# Layer.net
KiCad netlist of a schematic drawn in EAGLE
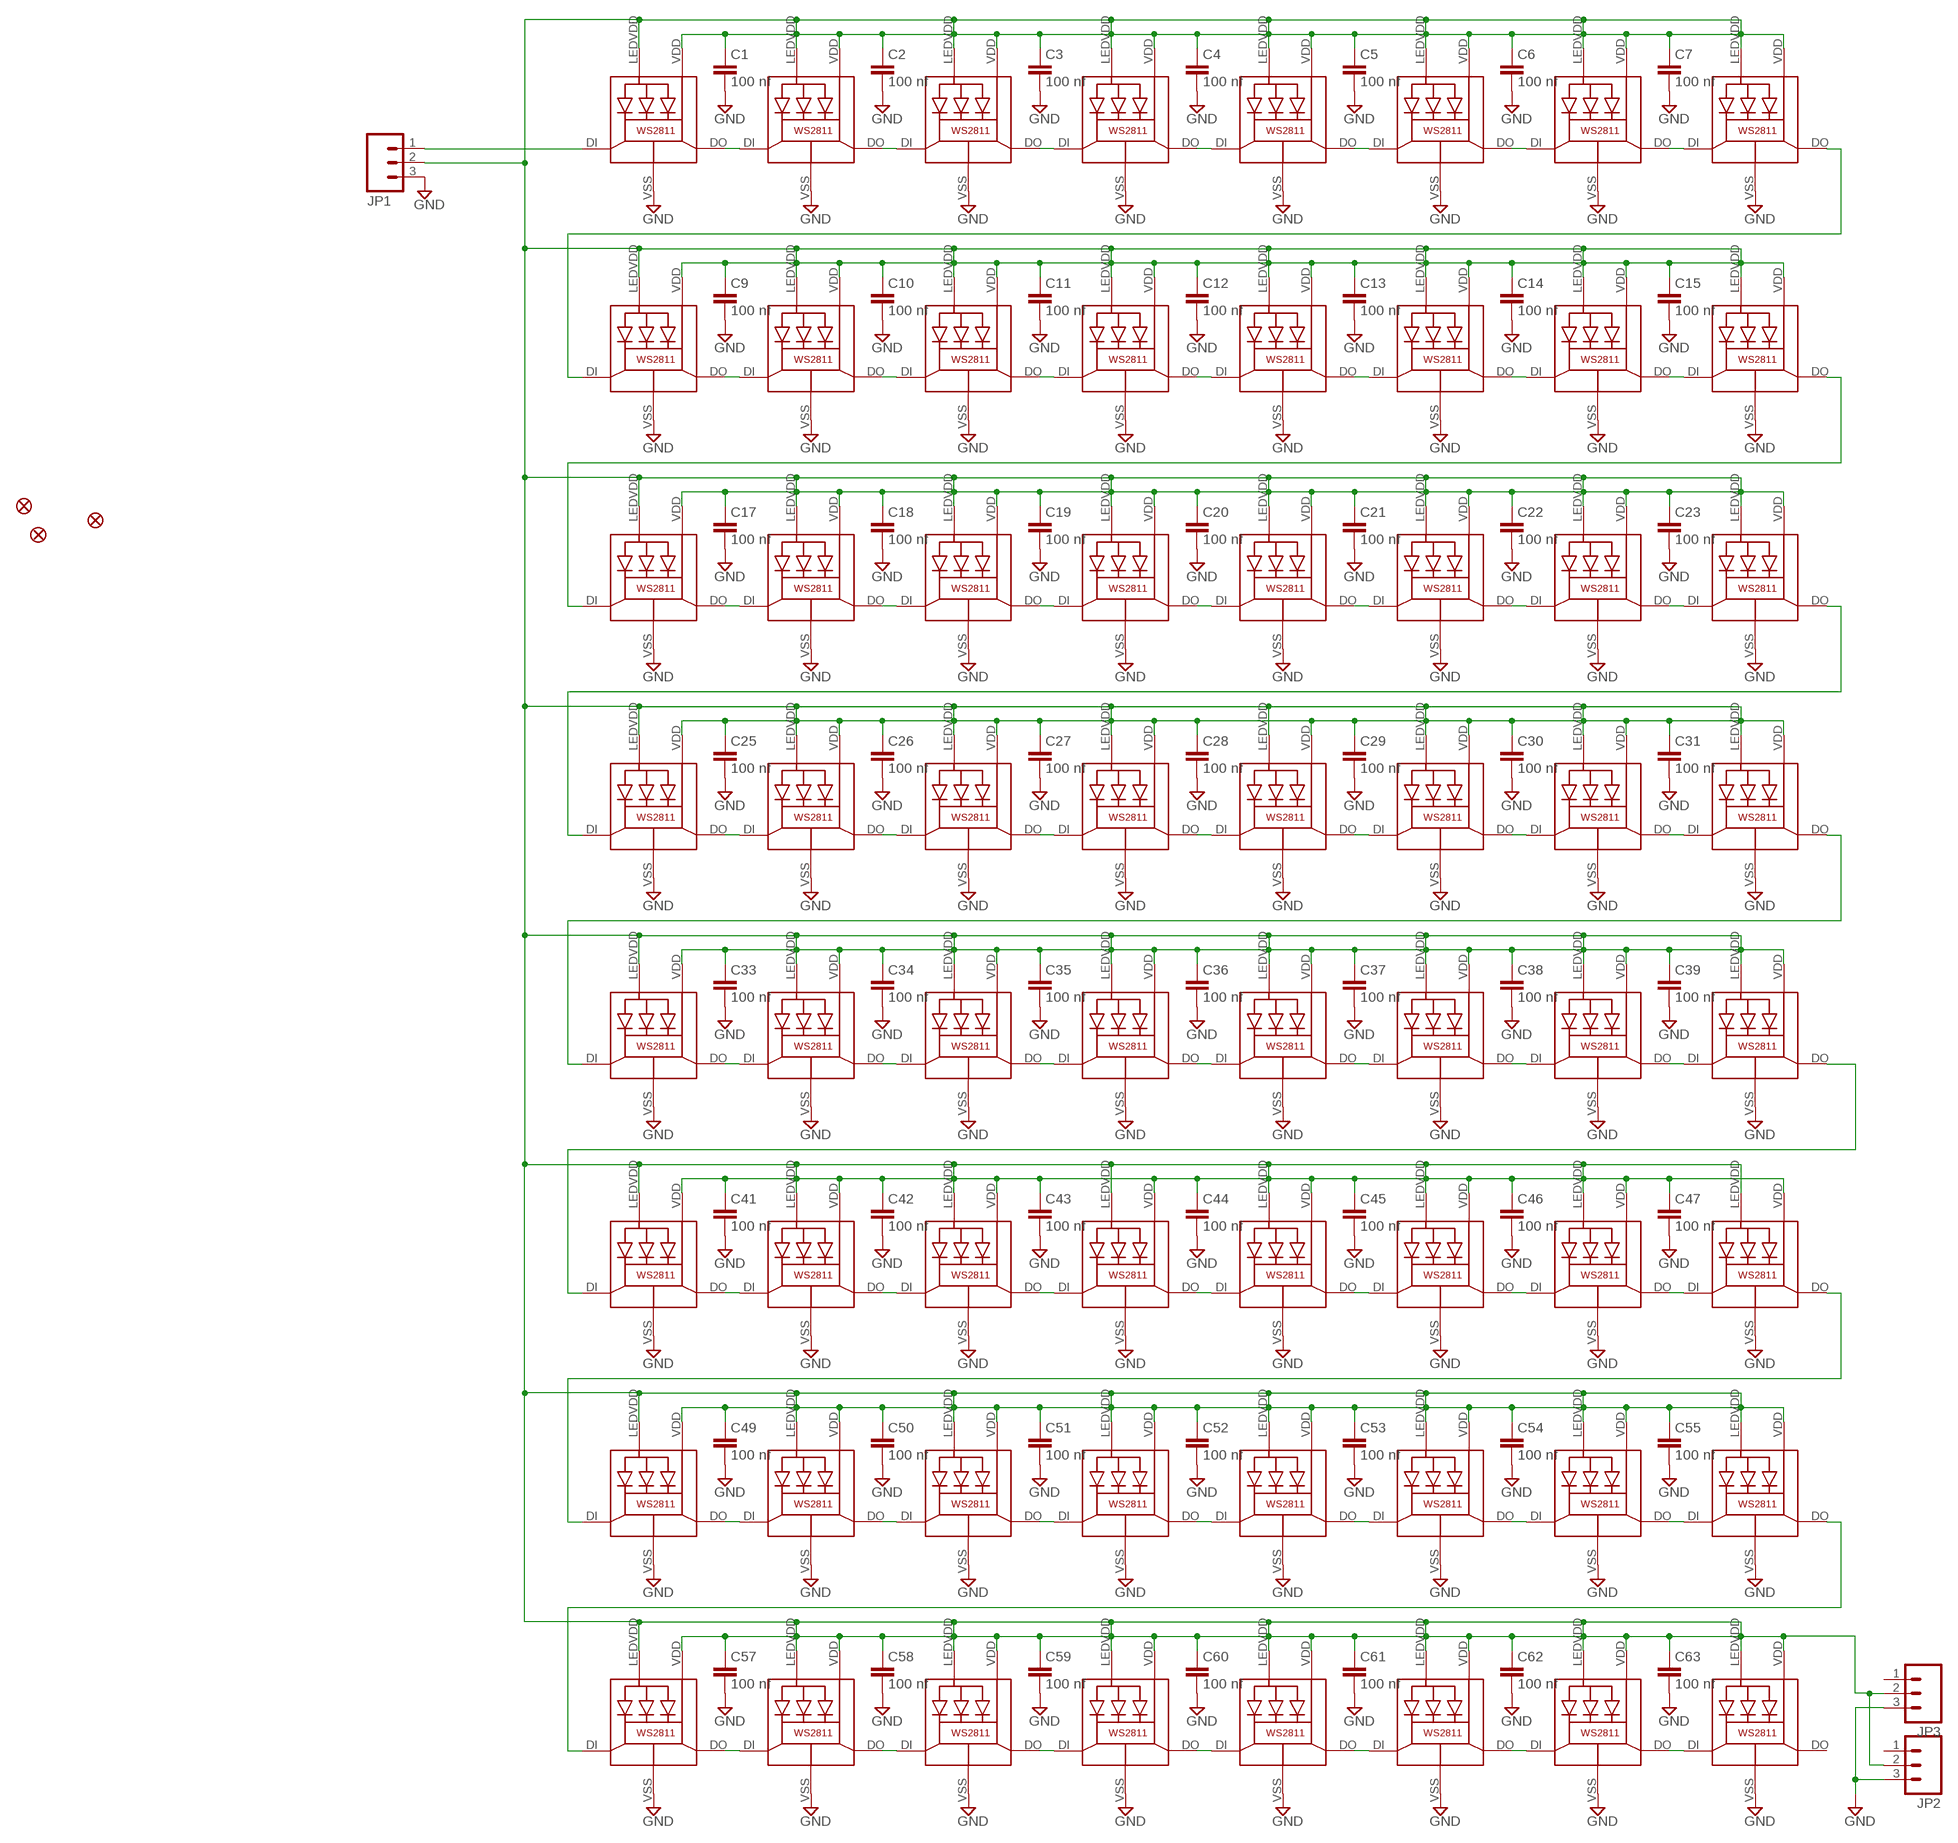
[diagram p0: schematic, sheet 1]

(export (version "E")
  (design (tool "Eeschema 10.0.6"))
  (components
    (comp (ref "C1")
      (value "100 nf")
      (footprint "eagle-import:C0805")
      (libsource (lib "eagle-import") (part "C-EUC0805"))
    )
    (comp (ref "C2")
      (value "100 nf")
      (footprint "eagle-import:C0805")
      (libsource (lib "eagle-import") (part "C-EUC0805"))
    )
    (comp (ref "C3")
      (value "100 nf")
      (footprint "eagle-import:C0805")
      (libsource (lib "eagle-import") (part "C-EUC0805"))
    )
    (comp (ref "C4")
      (value "100 nf")
      (footprint "eagle-import:C0805")
      (libsource (lib "eagle-import") (part "C-EUC0805"))
    )
    (comp (ref "C5")
      (value "100 nf")
      (footprint "eagle-import:C0805")
      (libsource (lib "eagle-import") (part "C-EUC0805"))
    )
    (comp (ref "C6")
      (value "100 nf")
      (footprint "eagle-import:C0805")
      (libsource (lib "eagle-import") (part "C-EUC0805"))
    )
    (comp (ref "C7")
      (value "100 nf")
      (footprint "eagle-import:C0805")
      (libsource (lib "eagle-import") (part "C-EUC0805"))
    )
    (comp (ref "C9")
      (value "100 nf")
      (footprint "eagle-import:C0805")
      (libsource (lib "eagle-import") (part "C-EUC0805"))
    )
    (comp (ref "C10")
      (value "100 nf")
      (footprint "eagle-import:C0805")
      (libsource (lib "eagle-import") (part "C-EUC0805"))
    )
    (comp (ref "C11")
      (value "100 nf")
      (footprint "eagle-import:C0805")
      (libsource (lib "eagle-import") (part "C-EUC0805"))
    )
    (comp (ref "C12")
      (value "100 nf")
      (footprint "eagle-import:C0805")
      (libsource (lib "eagle-import") (part "C-EUC0805"))
    )
    (comp (ref "C13")
      (value "100 nf")
      (footprint "eagle-import:C0805")
      (libsource (lib "eagle-import") (part "C-EUC0805"))
    )
    (comp (ref "C14")
      (value "100 nf")
      (footprint "eagle-import:C0805")
      (libsource (lib "eagle-import") (part "C-EUC0805"))
    )
    (comp (ref "C15")
      (value "100 nf")
      (footprint "eagle-import:C0805")
      (libsource (lib "eagle-import") (part "C-EUC0805"))
    )
    (comp (ref "C17")
      (value "100 nf")
      (footprint "eagle-import:C0805")
      (libsource (lib "eagle-import") (part "C-EUC0805"))
    )
    (comp (ref "C18")
      (value "100 nf")
      (footprint "eagle-import:C0805")
      (libsource (lib "eagle-import") (part "C-EUC0805"))
    )
    (comp (ref "C19")
      (value "100 nf")
      (footprint "eagle-import:C0805")
      (libsource (lib "eagle-import") (part "C-EUC0805"))
    )
    (comp (ref "C20")
      (value "100 nf")
      (footprint "eagle-import:C0805")
      (libsource (lib "eagle-import") (part "C-EUC0805"))
    )
    (comp (ref "C21")
      (value "100 nf")
      (footprint "eagle-import:C0805")
      (libsource (lib "eagle-import") (part "C-EUC0805"))
    )
    (comp (ref "C22")
      (value "100 nf")
      (footprint "eagle-import:C0805")
      (libsource (lib "eagle-import") (part "C-EUC0805"))
    )
    (comp (ref "C23")
      (value "100 nf")
      (footprint "eagle-import:C0805")
      (libsource (lib "eagle-import") (part "C-EUC0805"))
    )
    (comp (ref "C25")
      (value "100 nf")
      (footprint "eagle-import:C0805")
      (libsource (lib "eagle-import") (part "C-EUC0805"))
    )
    (comp (ref "C26")
      (value "100 nf")
      (footprint "eagle-import:C0805")
      (libsource (lib "eagle-import") (part "C-EUC0805"))
    )
    (comp (ref "C27")
      (value "100 nf")
      (footprint "eagle-import:C0805")
      (libsource (lib "eagle-import") (part "C-EUC0805"))
    )
    (comp (ref "C28")
      (value "100 nf")
      (footprint "eagle-import:C0805")
      (libsource (lib "eagle-import") (part "C-EUC0805"))
    )
    (comp (ref "C29")
      (value "100 nf")
      (footprint "eagle-import:C0805")
      (libsource (lib "eagle-import") (part "C-EUC0805"))
    )
    (comp (ref "C30")
      (value "100 nf")
      (footprint "eagle-import:C0805")
      (libsource (lib "eagle-import") (part "C-EUC0805"))
    )
    (comp (ref "C31")
      (value "100 nf")
      (footprint "eagle-import:C0805")
      (libsource (lib "eagle-import") (part "C-EUC0805"))
    )
    (comp (ref "C33")
      (value "100 nf")
      (footprint "eagle-import:C0805")
      (libsource (lib "eagle-import") (part "C-EUC0805"))
    )
    (comp (ref "C34")
      (value "100 nf")
      (footprint "eagle-import:C0805")
      (libsource (lib "eagle-import") (part "C-EUC0805"))
    )
    (comp (ref "C35")
      (value "100 nf")
      (footprint "eagle-import:C0805")
      (libsource (lib "eagle-import") (part "C-EUC0805"))
    )
    (comp (ref "C36")
      (value "100 nf")
      (footprint "eagle-import:C0805")
      (libsource (lib "eagle-import") (part "C-EUC0805"))
    )
    (comp (ref "C37")
      (value "100 nf")
      (footprint "eagle-import:C0805")
      (libsource (lib "eagle-import") (part "C-EUC0805"))
    )
    (comp (ref "C38")
      (value "100 nf")
      (footprint "eagle-import:C0805")
      (libsource (lib "eagle-import") (part "C-EUC0805"))
    )
    (comp (ref "C39")
      (value "100 nf")
      (footprint "eagle-import:C0805")
      (libsource (lib "eagle-import") (part "C-EUC0805"))
    )
    (comp (ref "C41")
      (value "100 nf")
      (footprint "eagle-import:C0805")
      (libsource (lib "eagle-import") (part "C-EUC0805"))
    )
    (comp (ref "C42")
      (value "100 nf")
      (footprint "eagle-import:C0805")
      (libsource (lib "eagle-import") (part "C-EUC0805"))
    )
    (comp (ref "C43")
      (value "100 nf")
      (footprint "eagle-import:C0805")
      (libsource (lib "eagle-import") (part "C-EUC0805"))
    )
    (comp (ref "C44")
      (value "100 nf")
      (footprint "eagle-import:C0805")
      (libsource (lib "eagle-import") (part "C-EUC0805"))
    )
    (comp (ref "C45")
      (value "100 nf")
      (footprint "eagle-import:C0805")
      (libsource (lib "eagle-import") (part "C-EUC0805"))
    )
    (comp (ref "C46")
      (value "100 nf")
      (footprint "eagle-import:C0805")
      (libsource (lib "eagle-import") (part "C-EUC0805"))
    )
    (comp (ref "C47")
      (value "100 nf")
      (footprint "eagle-import:C0805")
      (libsource (lib "eagle-import") (part "C-EUC0805"))
    )
    (comp (ref "C49")
      (value "100 nf")
      (footprint "eagle-import:C0805")
      (libsource (lib "eagle-import") (part "C-EUC0805"))
    )
    (comp (ref "C50")
      (value "100 nf")
      (footprint "eagle-import:C0805")
      (libsource (lib "eagle-import") (part "C-EUC0805"))
    )
    (comp (ref "C51")
      (value "100 nf")
      (footprint "eagle-import:C0805")
      (libsource (lib "eagle-import") (part "C-EUC0805"))
    )
    (comp (ref "C52")
      (value "100 nf")
      (footprint "eagle-import:C0805")
      (libsource (lib "eagle-import") (part "C-EUC0805"))
    )
    (comp (ref "C53")
      (value "100 nf")
      (footprint "eagle-import:C0805")
      (libsource (lib "eagle-import") (part "C-EUC0805"))
    )
    (comp (ref "C54")
      (value "100 nf")
      (footprint "eagle-import:C0805")
      (libsource (lib "eagle-import") (part "C-EUC0805"))
    )
    (comp (ref "C55")
      (value "100 nf")
      (footprint "eagle-import:C0805")
      (libsource (lib "eagle-import") (part "C-EUC0805"))
    )
    (comp (ref "C57")
      (value "100 nf")
      (footprint "eagle-import:C0805")
      (libsource (lib "eagle-import") (part "C-EUC0805"))
    )
    (comp (ref "C58")
      (value "100 nf")
      (footprint "eagle-import:C0805")
      (libsource (lib "eagle-import") (part "C-EUC0805"))
    )
    (comp (ref "C59")
      (value "100 nf")
      (footprint "eagle-import:C0805")
      (libsource (lib "eagle-import") (part "C-EUC0805"))
    )
    (comp (ref "C60")
      (value "100 nf")
      (footprint "eagle-import:C0805")
      (libsource (lib "eagle-import") (part "C-EUC0805"))
    )
    (comp (ref "C61")
      (value "100 nf")
      (footprint "eagle-import:C0805")
      (libsource (lib "eagle-import") (part "C-EUC0805"))
    )
    (comp (ref "C62")
      (value "100 nf")
      (footprint "eagle-import:C0805")
      (libsource (lib "eagle-import") (part "C-EUC0805"))
    )
    (comp (ref "C63")
      (value "100 nf")
      (footprint "eagle-import:C0805")
      (libsource (lib "eagle-import") (part "C-EUC0805"))
    )
    (comp (ref "FID1")
      (value "FIDUCIAL\"\"")
      (footprint "eagle-import:FIDUCIAL_1MM")
      (libsource (lib "eagle-import") (part "FIDUCIAL{dblquote}{dblquote}"))
    )
    (comp (ref "FID2")
      (value "FIDUCIAL\"\"")
      (footprint "eagle-import:FIDUCIAL_1MM")
      (libsource (lib "eagle-import") (part "FIDUCIAL{dblquote}{dblquote}"))
    )
    (comp (ref "FID3")
      (value "FIDUCIAL\"\"")
      (footprint "eagle-import:FIDUCIAL_1MM")
      (libsource (lib "eagle-import") (part "FIDUCIAL{dblquote}{dblquote}"))
    )
    (comp (ref "JP1")
      (value "M03PTH")
      (footprint "eagle-import:1X03")
      (libsource (lib "eagle-import") (part "M03PTH"))
    )
    (comp (ref "JP2")
      (value "M03PTH")
      (footprint "eagle-import:1X03")
      (libsource (lib "eagle-import") (part "M03PTH"))
    )
    (comp (ref "JP3")
      (value "M03PTH")
      (footprint "eagle-import:1X03")
      (libsource (lib "eagle-import") (part "M03PTH"))
    )
    (comp (ref "LED1")
      (value "WS28115050")
      (footprint "eagle-import:WS28115050")
      (fields (field (name "SPICEPREFIX") "X"))
      (libsource (lib "eagle-import") (part "WS28115050"))
    )
    (comp (ref "LED2")
      (value "WS28115050")
      (footprint "eagle-import:WS28115050")
      (libsource (lib "eagle-import") (part "WS28115050"))
    )
    (comp (ref "LED3")
      (value "WS28115050")
      (footprint "eagle-import:WS28115050")
      (libsource (lib "eagle-import") (part "WS28115050"))
    )
    (comp (ref "LED4")
      (value "WS28115050")
      (footprint "eagle-import:WS28115050")
      (libsource (lib "eagle-import") (part "WS28115050"))
    )
    (comp (ref "LED5")
      (value "WS28115050")
      (footprint "eagle-import:WS28115050")
      (libsource (lib "eagle-import") (part "WS28115050"))
    )
    (comp (ref "LED6")
      (value "WS28115050")
      (footprint "eagle-import:WS28115050")
      (libsource (lib "eagle-import") (part "WS28115050"))
    )
    (comp (ref "LED7")
      (value "WS28115050")
      (footprint "eagle-import:WS28115050")
      (libsource (lib "eagle-import") (part "WS28115050"))
    )
    (comp (ref "LED8")
      (value "WS28115050")
      (footprint "eagle-import:WS28115050")
      (libsource (lib "eagle-import") (part "WS28115050"))
    )
    (comp (ref "LED9")
      (value "WS28115050")
      (footprint "eagle-import:WS28115050")
      (libsource (lib "eagle-import") (part "WS28115050"))
    )
    (comp (ref "LED10")
      (value "WS28115050")
      (footprint "eagle-import:WS28115050")
      (libsource (lib "eagle-import") (part "WS28115050"))
    )
    (comp (ref "LED11")
      (value "WS28115050")
      (footprint "eagle-import:WS28115050")
      (libsource (lib "eagle-import") (part "WS28115050"))
    )
    (comp (ref "LED12")
      (value "WS28115050")
      (footprint "eagle-import:WS28115050")
      (libsource (lib "eagle-import") (part "WS28115050"))
    )
    (comp (ref "LED13")
      (value "WS28115050")
      (footprint "eagle-import:WS28115050")
      (libsource (lib "eagle-import") (part "WS28115050"))
    )
    (comp (ref "LED14")
      (value "WS28115050")
      (footprint "eagle-import:WS28115050")
      (libsource (lib "eagle-import") (part "WS28115050"))
    )
    (comp (ref "LED15")
      (value "WS28115050")
      (footprint "eagle-import:WS28115050")
      (libsource (lib "eagle-import") (part "WS28115050"))
    )
    (comp (ref "LED16")
      (value "WS28115050")
      (footprint "eagle-import:WS28115050")
      (libsource (lib "eagle-import") (part "WS28115050"))
    )
    (comp (ref "LED17")
      (value "WS28115050")
      (footprint "eagle-import:WS28115050")
      (libsource (lib "eagle-import") (part "WS28115050"))
    )
    (comp (ref "LED18")
      (value "WS28115050")
      (footprint "eagle-import:WS28115050")
      (libsource (lib "eagle-import") (part "WS28115050"))
    )
    (comp (ref "LED19")
      (value "WS28115050")
      (footprint "eagle-import:WS28115050")
      (libsource (lib "eagle-import") (part "WS28115050"))
    )
    (comp (ref "LED20")
      (value "WS28115050")
      (footprint "eagle-import:WS28115050")
      (libsource (lib "eagle-import") (part "WS28115050"))
    )
    (comp (ref "LED21")
      (value "WS28115050")
      (footprint "eagle-import:WS28115050")
      (libsource (lib "eagle-import") (part "WS28115050"))
    )
    (comp (ref "LED22")
      (value "WS28115050")
      (footprint "eagle-import:WS28115050")
      (libsource (lib "eagle-import") (part "WS28115050"))
    )
    (comp (ref "LED23")
      (value "WS28115050")
      (footprint "eagle-import:WS28115050")
      (libsource (lib "eagle-import") (part "WS28115050"))
    )
    (comp (ref "LED24")
      (value "WS28115050")
      (footprint "eagle-import:WS28115050")
      (libsource (lib "eagle-import") (part "WS28115050"))
    )
    (comp (ref "LED25")
      (value "WS28115050")
      (footprint "eagle-import:WS28115050")
      (libsource (lib "eagle-import") (part "WS28115050"))
    )
    (comp (ref "LED26")
      (value "WS28115050")
      (footprint "eagle-import:WS28115050")
      (libsource (lib "eagle-import") (part "WS28115050"))
    )
    (comp (ref "LED27")
      (value "WS28115050")
      (footprint "eagle-import:WS28115050")
      (libsource (lib "eagle-import") (part "WS28115050"))
    )
    (comp (ref "LED28")
      (value "WS28115050")
      (footprint "eagle-import:WS28115050")
      (libsource (lib "eagle-import") (part "WS28115050"))
    )
    (comp (ref "LED29")
      (value "WS28115050")
      (footprint "eagle-import:WS28115050")
      (libsource (lib "eagle-import") (part "WS28115050"))
    )
    (comp (ref "LED30")
      (value "WS28115050")
      (footprint "eagle-import:WS28115050")
      (libsource (lib "eagle-import") (part "WS28115050"))
    )
    (comp (ref "LED31")
      (value "WS28115050")
      (footprint "eagle-import:WS28115050")
      (libsource (lib "eagle-import") (part "WS28115050"))
    )
    (comp (ref "LED32")
      (value "WS28115050")
      (footprint "eagle-import:WS28115050")
      (libsource (lib "eagle-import") (part "WS28115050"))
    )
    (comp (ref "LED33")
      (value "WS28115050")
      (footprint "eagle-import:WS28115050")
      (libsource (lib "eagle-import") (part "WS28115050"))
    )
    (comp (ref "LED34")
      (value "WS28115050")
      (footprint "eagle-import:WS28115050")
      (libsource (lib "eagle-import") (part "WS28115050"))
    )
    (comp (ref "LED35")
      (value "WS28115050")
      (footprint "eagle-import:WS28115050")
      (libsource (lib "eagle-import") (part "WS28115050"))
    )
    (comp (ref "LED36")
      (value "WS28115050")
      (footprint "eagle-import:WS28115050")
      (libsource (lib "eagle-import") (part "WS28115050"))
    )
    (comp (ref "LED37")
      (value "WS28115050")
      (footprint "eagle-import:WS28115050")
      (libsource (lib "eagle-import") (part "WS28115050"))
    )
    (comp (ref "LED38")
      (value "WS28115050")
      (footprint "eagle-import:WS28115050")
      (libsource (lib "eagle-import") (part "WS28115050"))
    )
    (comp (ref "LED39")
      (value "WS28115050")
      (footprint "eagle-import:WS28115050")
      (libsource (lib "eagle-import") (part "WS28115050"))
    )
    (comp (ref "LED40")
      (value "WS28115050")
      (footprint "eagle-import:WS28115050")
      (libsource (lib "eagle-import") (part "WS28115050"))
    )
    (comp (ref "LED41")
      (value "WS28115050")
      (footprint "eagle-import:WS28115050")
      (libsource (lib "eagle-import") (part "WS28115050"))
    )
    (comp (ref "LED42")
      (value "WS28115050")
      (footprint "eagle-import:WS28115050")
      (libsource (lib "eagle-import") (part "WS28115050"))
    )
    (comp (ref "LED43")
      (value "WS28115050")
      (footprint "eagle-import:WS28115050")
      (libsource (lib "eagle-import") (part "WS28115050"))
    )
    (comp (ref "LED44")
      (value "WS28115050")
      (footprint "eagle-import:WS28115050")
      (libsource (lib "eagle-import") (part "WS28115050"))
    )
    (comp (ref "LED45")
      (value "WS28115050")
      (footprint "eagle-import:WS28115050")
      (libsource (lib "eagle-import") (part "WS28115050"))
    )
    (comp (ref "LED46")
      (value "WS28115050")
      (footprint "eagle-import:WS28115050")
      (libsource (lib "eagle-import") (part "WS28115050"))
    )
    (comp (ref "LED47")
      (value "WS28115050")
      (footprint "eagle-import:WS28115050")
      (libsource (lib "eagle-import") (part "WS28115050"))
    )
    (comp (ref "LED48")
      (value "WS28115050")
      (footprint "eagle-import:WS28115050")
      (libsource (lib "eagle-import") (part "WS28115050"))
    )
    (comp (ref "LED49")
      (value "WS28115050")
      (footprint "eagle-import:WS28115050")
      (libsource (lib "eagle-import") (part "WS28115050"))
    )
    (comp (ref "LED50")
      (value "WS28115050")
      (footprint "eagle-import:WS28115050")
      (libsource (lib "eagle-import") (part "WS28115050"))
    )
    (comp (ref "LED51")
      (value "WS28115050")
      (footprint "eagle-import:WS28115050")
      (libsource (lib "eagle-import") (part "WS28115050"))
    )
    (comp (ref "LED52")
      (value "WS28115050")
      (footprint "eagle-import:WS28115050")
      (libsource (lib "eagle-import") (part "WS28115050"))
    )
    (comp (ref "LED53")
      (value "WS28115050")
      (footprint "eagle-import:WS28115050")
      (libsource (lib "eagle-import") (part "WS28115050"))
    )
    (comp (ref "LED54")
      (value "WS28115050")
      (footprint "eagle-import:WS28115050")
      (libsource (lib "eagle-import") (part "WS28115050"))
    )
    (comp (ref "LED55")
      (value "WS28115050")
      (footprint "eagle-import:WS28115050")
      (libsource (lib "eagle-import") (part "WS28115050"))
    )
    (comp (ref "LED56")
      (value "WS28115050")
      (footprint "eagle-import:WS28115050")
      (libsource (lib "eagle-import") (part "WS28115050"))
    )
    (comp (ref "LED57")
      (value "WS28115050")
      (footprint "eagle-import:WS28115050")
      (libsource (lib "eagle-import") (part "WS28115050"))
    )
    (comp (ref "LED58")
      (value "WS28115050")
      (footprint "eagle-import:WS28115050")
      (libsource (lib "eagle-import") (part "WS28115050"))
    )
    (comp (ref "LED59")
      (value "WS28115050")
      (footprint "eagle-import:WS28115050")
      (libsource (lib "eagle-import") (part "WS28115050"))
    )
    (comp (ref "LED60")
      (value "WS28115050")
      (footprint "eagle-import:WS28115050")
      (libsource (lib "eagle-import") (part "WS28115050"))
    )
    (comp (ref "LED61")
      (value "WS28115050")
      (footprint "eagle-import:WS28115050")
      (libsource (lib "eagle-import") (part "WS28115050"))
    )
    (comp (ref "LED62")
      (value "WS28115050")
      (footprint "eagle-import:WS28115050")
      (libsource (lib "eagle-import") (part "WS28115050"))
    )
    (comp (ref "LED63")
      (value "WS28115050")
      (footprint "eagle-import:WS28115050")
      (libsource (lib "eagle-import") (part "WS28115050"))
    )
    (comp (ref "LED64")
      (value "WS28115050")
      (footprint "eagle-import:WS28115050")
      (libsource (lib "eagle-import") (part "WS28115050"))
    )
  )
  (nets
    (net (code "1") (name "GND") (class "Default")
      (node (ref "C1") (pin "2") (pinfunction "2_2") (pintype "passive"))
      (node (ref "C10") (pin "2") (pinfunction "2_2") (pintype "passive"))
      (node (ref "C11") (pin "2") (pinfunction "2_2") (pintype "passive"))
      (node (ref "C12") (pin "2") (pinfunction "2_2") (pintype "passive"))
      (node (ref "C13") (pin "2") (pinfunction "2_2") (pintype "passive"))
      (node (ref "C14") (pin "2") (pinfunction "2_2") (pintype "passive"))
      (node (ref "C15") (pin "2") (pinfunction "2_2") (pintype "passive"))
      (node (ref "C17") (pin "2") (pinfunction "2_2") (pintype "passive"))
      (node (ref "C18") (pin "2") (pinfunction "2_2") (pintype "passive"))
      (node (ref "C19") (pin "2") (pinfunction "2_2") (pintype "passive"))
      (node (ref "C2") (pin "2") (pinfunction "2_2") (pintype "passive"))
      (node (ref "C20") (pin "2") (pinfunction "2_2") (pintype "passive"))
      (node (ref "C21") (pin "2") (pinfunction "2_2") (pintype "passive"))
      (node (ref "C22") (pin "2") (pinfunction "2_2") (pintype "passive"))
      (node (ref "C23") (pin "2") (pinfunction "2_2") (pintype "passive"))
      (node (ref "C25") (pin "2") (pinfunction "2_2") (pintype "passive"))
      (node (ref "C26") (pin "2") (pinfunction "2_2") (pintype "passive"))
      (node (ref "C27") (pin "2") (pinfunction "2_2") (pintype "passive"))
      (node (ref "C28") (pin "2") (pinfunction "2_2") (pintype "passive"))
      (node (ref "C29") (pin "2") (pinfunction "2_2") (pintype "passive"))
      (node (ref "C3") (pin "2") (pinfunction "2_2") (pintype "passive"))
      (node (ref "C30") (pin "2") (pinfunction "2_2") (pintype "passive"))
      (node (ref "C31") (pin "2") (pinfunction "2_2") (pintype "passive"))
      (node (ref "C33") (pin "2") (pinfunction "2_2") (pintype "passive"))
      (node (ref "C34") (pin "2") (pinfunction "2_2") (pintype "passive"))
      (node (ref "C35") (pin "2") (pinfunction "2_2") (pintype "passive"))
      (node (ref "C36") (pin "2") (pinfunction "2_2") (pintype "passive"))
      (node (ref "C37") (pin "2") (pinfunction "2_2") (pintype "passive"))
      (node (ref "C38") (pin "2") (pinfunction "2_2") (pintype "passive"))
      (node (ref "C39") (pin "2") (pinfunction "2_2") (pintype "passive"))
      (node (ref "C4") (pin "2") (pinfunction "2_2") (pintype "passive"))
      (node (ref "C41") (pin "2") (pinfunction "2_2") (pintype "passive"))
      (node (ref "C42") (pin "2") (pinfunction "2_2") (pintype "passive"))
      (node (ref "C43") (pin "2") (pinfunction "2_2") (pintype "passive"))
      (node (ref "C44") (pin "2") (pinfunction "2_2") (pintype "passive"))
      (node (ref "C45") (pin "2") (pinfunction "2_2") (pintype "passive"))
      (node (ref "C46") (pin "2") (pinfunction "2_2") (pintype "passive"))
      (node (ref "C47") (pin "2") (pinfunction "2_2") (pintype "passive"))
      (node (ref "C49") (pin "2") (pinfunction "2_2") (pintype "passive"))
      (node (ref "C5") (pin "2") (pinfunction "2_2") (pintype "passive"))
      (node (ref "C50") (pin "2") (pinfunction "2_2") (pintype "passive"))
      (node (ref "C51") (pin "2") (pinfunction "2_2") (pintype "passive"))
      (node (ref "C52") (pin "2") (pinfunction "2_2") (pintype "passive"))
      (node (ref "C53") (pin "2") (pinfunction "2_2") (pintype "passive"))
      (node (ref "C54") (pin "2") (pinfunction "2_2") (pintype "passive"))
      (node (ref "C55") (pin "2") (pinfunction "2_2") (pintype "passive"))
      (node (ref "C57") (pin "2") (pinfunction "2_2") (pintype "passive"))
      (node (ref "C58") (pin "2") (pinfunction "2_2") (pintype "passive"))
      (node (ref "C59") (pin "2") (pinfunction "2_2") (pintype "passive"))
      (node (ref "C6") (pin "2") (pinfunction "2_2") (pintype "passive"))
      (node (ref "C60") (pin "2") (pinfunction "2_2") (pintype "passive"))
      (node (ref "C61") (pin "2") (pinfunction "2_2") (pintype "passive"))
      (node (ref "C62") (pin "2") (pinfunction "2_2") (pintype "passive"))
      (node (ref "C63") (pin "2") (pinfunction "2_2") (pintype "passive"))
      (node (ref "C7") (pin "2") (pinfunction "2_2") (pintype "passive"))
      (node (ref "C9") (pin "2") (pinfunction "2_2") (pintype "passive"))
      (node (ref "JP1") (pin "3") (pinfunction "3_3") (pintype "passive"))
      (node (ref "JP2") (pin "3") (pinfunction "3_3") (pintype "passive"))
      (node (ref "JP3") (pin "3") (pinfunction "3_3") (pintype "passive"))
      (node (ref "LED1") (pin "VSS") (pinfunction "GND_VSS") (pintype "power_in"))
      (node (ref "LED10") (pin "VSS") (pinfunction "GND_VSS") (pintype "power_in"))
      (node (ref "LED11") (pin "VSS") (pinfunction "GND_VSS") (pintype "power_in"))
      (node (ref "LED12") (pin "VSS") (pinfunction "GND_VSS") (pintype "power_in"))
      (node (ref "LED13") (pin "VSS") (pinfunction "GND_VSS") (pintype "power_in"))
      (node (ref "LED14") (pin "VSS") (pinfunction "GND_VSS") (pintype "power_in"))
      (node (ref "LED15") (pin "VSS") (pinfunction "GND_VSS") (pintype "power_in"))
      (node (ref "LED16") (pin "VSS") (pinfunction "GND_VSS") (pintype "power_in"))
      (node (ref "LED17") (pin "VSS") (pinfunction "GND_VSS") (pintype "power_in"))
      (node (ref "LED18") (pin "VSS") (pinfunction "GND_VSS") (pintype "power_in"))
      (node (ref "LED19") (pin "VSS") (pinfunction "GND_VSS") (pintype "power_in"))
      (node (ref "LED2") (pin "VSS") (pinfunction "GND_VSS") (pintype "power_in"))
      (node (ref "LED20") (pin "VSS") (pinfunction "GND_VSS") (pintype "power_in"))
      (node (ref "LED21") (pin "VSS") (pinfunction "GND_VSS") (pintype "power_in"))
      (node (ref "LED22") (pin "VSS") (pinfunction "GND_VSS") (pintype "power_in"))
      (node (ref "LED23") (pin "VSS") (pinfunction "GND_VSS") (pintype "power_in"))
      (node (ref "LED24") (pin "VSS") (pinfunction "GND_VSS") (pintype "power_in"))
      (node (ref "LED25") (pin "VSS") (pinfunction "GND_VSS") (pintype "power_in"))
      (node (ref "LED26") (pin "VSS") (pinfunction "GND_VSS") (pintype "power_in"))
      (node (ref "LED27") (pin "VSS") (pinfunction "GND_VSS") (pintype "power_in"))
      (node (ref "LED28") (pin "VSS") (pinfunction "GND_VSS") (pintype "power_in"))
      (node (ref "LED29") (pin "VSS") (pinfunction "GND_VSS") (pintype "power_in"))
      (node (ref "LED3") (pin "VSS") (pinfunction "GND_VSS") (pintype "power_in"))
      (node (ref "LED30") (pin "VSS") (pinfunction "GND_VSS") (pintype "power_in"))
      (node (ref "LED31") (pin "VSS") (pinfunction "GND_VSS") (pintype "power_in"))
      (node (ref "LED32") (pin "VSS") (pinfunction "GND_VSS") (pintype "power_in"))
      (node (ref "LED33") (pin "VSS") (pinfunction "GND_VSS") (pintype "power_in"))
      (node (ref "LED34") (pin "VSS") (pinfunction "GND_VSS") (pintype "power_in"))
      (node (ref "LED35") (pin "VSS") (pinfunction "GND_VSS") (pintype "power_in"))
      (node (ref "LED36") (pin "VSS") (pinfunction "GND_VSS") (pintype "power_in"))
      (node (ref "LED37") (pin "VSS") (pinfunction "GND_VSS") (pintype "power_in"))
      (node (ref "LED38") (pin "VSS") (pinfunction "GND_VSS") (pintype "power_in"))
      (node (ref "LED39") (pin "VSS") (pinfunction "GND_VSS") (pintype "power_in"))
      (node (ref "LED4") (pin "VSS") (pinfunction "GND_VSS") (pintype "power_in"))
      (node (ref "LED40") (pin "VSS") (pinfunction "GND_VSS") (pintype "power_in"))
      (node (ref "LED41") (pin "VSS") (pinfunction "GND_VSS") (pintype "power_in"))
      (node (ref "LED42") (pin "VSS") (pinfunction "GND_VSS") (pintype "power_in"))
      (node (ref "LED43") (pin "VSS") (pinfunction "GND_VSS") (pintype "power_in"))
      (node (ref "LED44") (pin "VSS") (pinfunction "GND_VSS") (pintype "power_in"))
      (node (ref "LED45") (pin "VSS") (pinfunction "GND_VSS") (pintype "power_in"))
      (node (ref "LED46") (pin "VSS") (pinfunction "GND_VSS") (pintype "power_in"))
      (node (ref "LED47") (pin "VSS") (pinfunction "GND_VSS") (pintype "power_in"))
      (node (ref "LED48") (pin "VSS") (pinfunction "GND_VSS") (pintype "power_in"))
      (node (ref "LED49") (pin "VSS") (pinfunction "GND_VSS") (pintype "power_in"))
      (node (ref "LED5") (pin "VSS") (pinfunction "GND_VSS") (pintype "power_in"))
      (node (ref "LED50") (pin "VSS") (pinfunction "GND_VSS") (pintype "power_in"))
      (node (ref "LED51") (pin "VSS") (pinfunction "GND_VSS") (pintype "power_in"))
      (node (ref "LED52") (pin "VSS") (pinfunction "GND_VSS") (pintype "power_in"))
      (node (ref "LED53") (pin "VSS") (pinfunction "GND_VSS") (pintype "power_in"))
      (node (ref "LED54") (pin "VSS") (pinfunction "GND_VSS") (pintype "power_in"))
      (node (ref "LED55") (pin "VSS") (pinfunction "GND_VSS") (pintype "power_in"))
      (node (ref "LED56") (pin "VSS") (pinfunction "GND_VSS") (pintype "power_in"))
      (node (ref "LED57") (pin "VSS") (pinfunction "GND_VSS") (pintype "power_in"))
      (node (ref "LED58") (pin "VSS") (pinfunction "GND_VSS") (pintype "power_in"))
      (node (ref "LED59") (pin "VSS") (pinfunction "GND_VSS") (pintype "power_in"))
      (node (ref "LED6") (pin "VSS") (pinfunction "GND_VSS") (pintype "power_in"))
      (node (ref "LED60") (pin "VSS") (pinfunction "GND_VSS") (pintype "power_in"))
      (node (ref "LED61") (pin "VSS") (pinfunction "GND_VSS") (pintype "power_in"))
      (node (ref "LED62") (pin "VSS") (pinfunction "GND_VSS") (pintype "power_in"))
      (node (ref "LED63") (pin "VSS") (pinfunction "GND_VSS") (pintype "power_in"))
      (node (ref "LED64") (pin "VSS") (pinfunction "GND_VSS") (pintype "power_in"))
      (node (ref "LED7") (pin "VSS") (pinfunction "GND_VSS") (pintype "power_in"))
      (node (ref "LED8") (pin "VSS") (pinfunction "GND_VSS") (pintype "power_in"))
      (node (ref "LED9") (pin "VSS") (pinfunction "GND_VSS") (pintype "power_in"))
    )
    (net (code "2") (name "Net-(C1-Pad1)") (class "Default")
      (node (ref "C1") (pin "1") (pinfunction "1_1") (pintype "passive"))
      (node (ref "C10") (pin "1") (pinfunction "1_1") (pintype "passive"))
      (node (ref "C11") (pin "1") (pinfunction "1_1") (pintype "passive"))
      (node (ref "C12") (pin "1") (pinfunction "1_1") (pintype "passive"))
      (node (ref "C13") (pin "1") (pinfunction "1_1") (pintype "passive"))
      (node (ref "C14") (pin "1") (pinfunction "1_1") (pintype "passive"))
      (node (ref "C15") (pin "1") (pinfunction "1_1") (pintype "passive"))
      (node (ref "C17") (pin "1") (pinfunction "1_1") (pintype "passive"))
      (node (ref "C18") (pin "1") (pinfunction "1_1") (pintype "passive"))
      (node (ref "C19") (pin "1") (pinfunction "1_1") (pintype "passive"))
      (node (ref "C2") (pin "1") (pinfunction "1_1") (pintype "passive"))
      (node (ref "C20") (pin "1") (pinfunction "1_1") (pintype "passive"))
      (node (ref "C21") (pin "1") (pinfunction "1_1") (pintype "passive"))
      (node (ref "C22") (pin "1") (pinfunction "1_1") (pintype "passive"))
      (node (ref "C23") (pin "1") (pinfunction "1_1") (pintype "passive"))
      (node (ref "C25") (pin "1") (pinfunction "1_1") (pintype "passive"))
      (node (ref "C26") (pin "1") (pinfunction "1_1") (pintype "passive"))
      (node (ref "C27") (pin "1") (pinfunction "1_1") (pintype "passive"))
      (node (ref "C28") (pin "1") (pinfunction "1_1") (pintype "passive"))
      (node (ref "C29") (pin "1") (pinfunction "1_1") (pintype "passive"))
      (node (ref "C3") (pin "1") (pinfunction "1_1") (pintype "passive"))
      (node (ref "C30") (pin "1") (pinfunction "1_1") (pintype "passive"))
      (node (ref "C31") (pin "1") (pinfunction "1_1") (pintype "passive"))
      (node (ref "C33") (pin "1") (pinfunction "1_1") (pintype "passive"))
      (node (ref "C34") (pin "1") (pinfunction "1_1") (pintype "passive"))
      (node (ref "C35") (pin "1") (pinfunction "1_1") (pintype "passive"))
      (node (ref "C36") (pin "1") (pinfunction "1_1") (pintype "passive"))
      (node (ref "C37") (pin "1") (pinfunction "1_1") (pintype "passive"))
      (node (ref "C38") (pin "1") (pinfunction "1_1") (pintype "passive"))
      (node (ref "C39") (pin "1") (pinfunction "1_1") (pintype "passive"))
      (node (ref "C4") (pin "1") (pinfunction "1_1") (pintype "passive"))
      (node (ref "C41") (pin "1") (pinfunction "1_1") (pintype "passive"))
      (node (ref "C42") (pin "1") (pinfunction "1_1") (pintype "passive"))
      (node (ref "C43") (pin "1") (pinfunction "1_1") (pintype "passive"))
      (node (ref "C44") (pin "1") (pinfunction "1_1") (pintype "passive"))
      (node (ref "C45") (pin "1") (pinfunction "1_1") (pintype "passive"))
      (node (ref "C46") (pin "1") (pinfunction "1_1") (pintype "passive"))
      (node (ref "C47") (pin "1") (pinfunction "1_1") (pintype "passive"))
      (node (ref "C49") (pin "1") (pinfunction "1_1") (pintype "passive"))
      (node (ref "C5") (pin "1") (pinfunction "1_1") (pintype "passive"))
      (node (ref "C50") (pin "1") (pinfunction "1_1") (pintype "passive"))
      (node (ref "C51") (pin "1") (pinfunction "1_1") (pintype "passive"))
      (node (ref "C52") (pin "1") (pinfunction "1_1") (pintype "passive"))
      (node (ref "C53") (pin "1") (pinfunction "1_1") (pintype "passive"))
      (node (ref "C54") (pin "1") (pinfunction "1_1") (pintype "passive"))
      (node (ref "C55") (pin "1") (pinfunction "1_1") (pintype "passive"))
      (node (ref "C57") (pin "1") (pinfunction "1_1") (pintype "passive"))
      (node (ref "C58") (pin "1") (pinfunction "1_1") (pintype "passive"))
      (node (ref "C59") (pin "1") (pinfunction "1_1") (pintype "passive"))
      (node (ref "C6") (pin "1") (pinfunction "1_1") (pintype "passive"))
      (node (ref "C60") (pin "1") (pinfunction "1_1") (pintype "passive"))
      (node (ref "C61") (pin "1") (pinfunction "1_1") (pintype "passive"))
      (node (ref "C62") (pin "1") (pinfunction "1_1") (pintype "passive"))
      (node (ref "C63") (pin "1") (pinfunction "1_1") (pintype "passive"))
      (node (ref "C7") (pin "1") (pinfunction "1_1") (pintype "passive"))
      (node (ref "C9") (pin "1") (pinfunction "1_1") (pintype "passive"))
      (node (ref "JP1") (pin "2") (pinfunction "2_2") (pintype "passive"))
      (node (ref "JP2") (pin "2") (pinfunction "2_2") (pintype "passive"))
      (node (ref "JP3") (pin "2") (pinfunction "2_2") (pintype "passive"))
      (node (ref "LED1") (pin "LEDVDD") (pinfunction "LEDVDD_LEDVDD") (pintype "power_in"))
      (node (ref "LED1") (pin "VDD") (pinfunction "VDD_VDD") (pintype "power_in"))
      (node (ref "LED10") (pin "LEDVDD") (pinfunction "LEDVDD_LEDVDD") (pintype "power_in"))
      (node (ref "LED10") (pin "VDD") (pinfunction "VDD_VDD") (pintype "power_in"))
      (node (ref "LED11") (pin "LEDVDD") (pinfunction "LEDVDD_LEDVDD") (pintype "power_in"))
      (node (ref "LED11") (pin "VDD") (pinfunction "VDD_VDD") (pintype "power_in"))
      (node (ref "LED12") (pin "LEDVDD") (pinfunction "LEDVDD_LEDVDD") (pintype "power_in"))
      (node (ref "LED12") (pin "VDD") (pinfunction "VDD_VDD") (pintype "power_in"))
      (node (ref "LED13") (pin "LEDVDD") (pinfunction "LEDVDD_LEDVDD") (pintype "power_in"))
      (node (ref "LED13") (pin "VDD") (pinfunction "VDD_VDD") (pintype "power_in"))
      (node (ref "LED14") (pin "LEDVDD") (pinfunction "LEDVDD_LEDVDD") (pintype "power_in"))
      (node (ref "LED14") (pin "VDD") (pinfunction "VDD_VDD") (pintype "power_in"))
      (node (ref "LED15") (pin "LEDVDD") (pinfunction "LEDVDD_LEDVDD") (pintype "power_in"))
      (node (ref "LED15") (pin "VDD") (pinfunction "VDD_VDD") (pintype "power_in"))
      (node (ref "LED16") (pin "LEDVDD") (pinfunction "LEDVDD_LEDVDD") (pintype "power_in"))
      (node (ref "LED16") (pin "VDD") (pinfunction "VDD_VDD") (pintype "power_in"))
      (node (ref "LED17") (pin "LEDVDD") (pinfunction "LEDVDD_LEDVDD") (pintype "power_in"))
      (node (ref "LED17") (pin "VDD") (pinfunction "VDD_VDD") (pintype "power_in"))
      (node (ref "LED18") (pin "LEDVDD") (pinfunction "LEDVDD_LEDVDD") (pintype "power_in"))
      (node (ref "LED18") (pin "VDD") (pinfunction "VDD_VDD") (pintype "power_in"))
      (node (ref "LED19") (pin "LEDVDD") (pinfunction "LEDVDD_LEDVDD") (pintype "power_in"))
      (node (ref "LED19") (pin "VDD") (pinfunction "VDD_VDD") (pintype "power_in"))
      (node (ref "LED2") (pin "LEDVDD") (pinfunction "LEDVDD_LEDVDD") (pintype "power_in"))
      (node (ref "LED2") (pin "VDD") (pinfunction "VDD_VDD") (pintype "power_in"))
      (node (ref "LED20") (pin "LEDVDD") (pinfunction "LEDVDD_LEDVDD") (pintype "power_in"))
      (node (ref "LED20") (pin "VDD") (pinfunction "VDD_VDD") (pintype "power_in"))
      (node (ref "LED21") (pin "LEDVDD") (pinfunction "LEDVDD_LEDVDD") (pintype "power_in"))
      (node (ref "LED21") (pin "VDD") (pinfunction "VDD_VDD") (pintype "power_in"))
      (node (ref "LED22") (pin "LEDVDD") (pinfunction "LEDVDD_LEDVDD") (pintype "power_in"))
      (node (ref "LED22") (pin "VDD") (pinfunction "VDD_VDD") (pintype "power_in"))
      (node (ref "LED23") (pin "LEDVDD") (pinfunction "LEDVDD_LEDVDD") (pintype "power_in"))
      (node (ref "LED23") (pin "VDD") (pinfunction "VDD_VDD") (pintype "power_in"))
      (node (ref "LED24") (pin "LEDVDD") (pinfunction "LEDVDD_LEDVDD") (pintype "power_in"))
      (node (ref "LED24") (pin "VDD") (pinfunction "VDD_VDD") (pintype "power_in"))
      (node (ref "LED25") (pin "LEDVDD") (pinfunction "LEDVDD_LEDVDD") (pintype "power_in"))
      (node (ref "LED25") (pin "VDD") (pinfunction "VDD_VDD") (pintype "power_in"))
      (node (ref "LED26") (pin "LEDVDD") (pinfunction "LEDVDD_LEDVDD") (pintype "power_in"))
      (node (ref "LED26") (pin "VDD") (pinfunction "VDD_VDD") (pintype "power_in"))
      (node (ref "LED27") (pin "LEDVDD") (pinfunction "LEDVDD_LEDVDD") (pintype "power_in"))
      (node (ref "LED27") (pin "VDD") (pinfunction "VDD_VDD") (pintype "power_in"))
      (node (ref "LED28") (pin "LEDVDD") (pinfunction "LEDVDD_LEDVDD") (pintype "power_in"))
      (node (ref "LED28") (pin "VDD") (pinfunction "VDD_VDD") (pintype "power_in"))
      (node (ref "LED29") (pin "LEDVDD") (pinfunction "LEDVDD_LEDVDD") (pintype "power_in"))
      (node (ref "LED29") (pin "VDD") (pinfunction "VDD_VDD") (pintype "power_in"))
      (node (ref "LED3") (pin "LEDVDD") (pinfunction "LEDVDD_LEDVDD") (pintype "power_in"))
      (node (ref "LED3") (pin "VDD") (pinfunction "VDD_VDD") (pintype "power_in"))
      (node (ref "LED30") (pin "LEDVDD") (pinfunction "LEDVDD_LEDVDD") (pintype "power_in"))
      (node (ref "LED30") (pin "VDD") (pinfunction "VDD_VDD") (pintype "power_in"))
      (node (ref "LED31") (pin "LEDVDD") (pinfunction "LEDVDD_LEDVDD") (pintype "power_in"))
      (node (ref "LED31") (pin "VDD") (pinfunction "VDD_VDD") (pintype "power_in"))
      (node (ref "LED32") (pin "LEDVDD") (pinfunction "LEDVDD_LEDVDD") (pintype "power_in"))
      (node (ref "LED32") (pin "VDD") (pinfunction "VDD_VDD") (pintype "power_in"))
      (node (ref "LED33") (pin "LEDVDD") (pinfunction "LEDVDD_LEDVDD") (pintype "power_in"))
      (node (ref "LED33") (pin "VDD") (pinfunction "VDD_VDD") (pintype "power_in"))
      (node (ref "LED34") (pin "LEDVDD") (pinfunction "LEDVDD_LEDVDD") (pintype "power_in"))
      (node (ref "LED34") (pin "VDD") (pinfunction "VDD_VDD") (pintype "power_in"))
      (node (ref "LED35") (pin "LEDVDD") (pinfunction "LEDVDD_LEDVDD") (pintype "power_in"))
      (node (ref "LED35") (pin "VDD") (pinfunction "VDD_VDD") (pintype "power_in"))
      (node (ref "LED36") (pin "LEDVDD") (pinfunction "LEDVDD_LEDVDD") (pintype "power_in"))
      (node (ref "LED36") (pin "VDD") (pinfunction "VDD_VDD") (pintype "power_in"))
      (node (ref "LED37") (pin "LEDVDD") (pinfunction "LEDVDD_LEDVDD") (pintype "power_in"))
      (node (ref "LED37") (pin "VDD") (pinfunction "VDD_VDD") (pintype "power_in"))
      (node (ref "LED38") (pin "LEDVDD") (pinfunction "LEDVDD_LEDVDD") (pintype "power_in"))
      (node (ref "LED38") (pin "VDD") (pinfunction "VDD_VDD") (pintype "power_in"))
      (node (ref "LED39") (pin "LEDVDD") (pinfunction "LEDVDD_LEDVDD") (pintype "power_in"))
      (node (ref "LED39") (pin "VDD") (pinfunction "VDD_VDD") (pintype "power_in"))
      (node (ref "LED4") (pin "LEDVDD") (pinfunction "LEDVDD_LEDVDD") (pintype "power_in"))
      (node (ref "LED4") (pin "VDD") (pinfunction "VDD_VDD") (pintype "power_in"))
      (node (ref "LED40") (pin "LEDVDD") (pinfunction "LEDVDD_LEDVDD") (pintype "power_in"))
      (node (ref "LED40") (pin "VDD") (pinfunction "VDD_VDD") (pintype "power_in"))
      (node (ref "LED41") (pin "LEDVDD") (pinfunction "LEDVDD_LEDVDD") (pintype "power_in"))
      (node (ref "LED41") (pin "VDD") (pinfunction "VDD_VDD") (pintype "power_in"))
      (node (ref "LED42") (pin "LEDVDD") (pinfunction "LEDVDD_LEDVDD") (pintype "power_in"))
      (node (ref "LED42") (pin "VDD") (pinfunction "VDD_VDD") (pintype "power_in"))
      (node (ref "LED43") (pin "LEDVDD") (pinfunction "LEDVDD_LEDVDD") (pintype "power_in"))
      (node (ref "LED43") (pin "VDD") (pinfunction "VDD_VDD") (pintype "power_in"))
      (node (ref "LED44") (pin "LEDVDD") (pinfunction "LEDVDD_LEDVDD") (pintype "power_in"))
      (node (ref "LED44") (pin "VDD") (pinfunction "VDD_VDD") (pintype "power_in"))
      (node (ref "LED45") (pin "LEDVDD") (pinfunction "LEDVDD_LEDVDD") (pintype "power_in"))
      (node (ref "LED45") (pin "VDD") (pinfunction "VDD_VDD") (pintype "power_in"))
      (node (ref "LED46") (pin "LEDVDD") (pinfunction "LEDVDD_LEDVDD") (pintype "power_in"))
      (node (ref "LED46") (pin "VDD") (pinfunction "VDD_VDD") (pintype "power_in"))
      (node (ref "LED47") (pin "LEDVDD") (pinfunction "LEDVDD_LEDVDD") (pintype "power_in"))
      (node (ref "LED47") (pin "VDD") (pinfunction "VDD_VDD") (pintype "power_in"))
      (node (ref "LED48") (pin "LEDVDD") (pinfunction "LEDVDD_LEDVDD") (pintype "power_in"))
      (node (ref "LED48") (pin "VDD") (pinfunction "VDD_VDD") (pintype "power_in"))
      (node (ref "LED49") (pin "LEDVDD") (pinfunction "LEDVDD_LEDVDD") (pintype "power_in"))
      (node (ref "LED49") (pin "VDD") (pinfunction "VDD_VDD") (pintype "power_in"))
      (node (ref "LED5") (pin "LEDVDD") (pinfunction "LEDVDD_LEDVDD") (pintype "power_in"))
      (node (ref "LED5") (pin "VDD") (pinfunction "VDD_VDD") (pintype "power_in"))
      (node (ref "LED50") (pin "LEDVDD") (pinfunction "LEDVDD_LEDVDD") (pintype "power_in"))
      (node (ref "LED50") (pin "VDD") (pinfunction "VDD_VDD") (pintype "power_in"))
      (node (ref "LED51") (pin "LEDVDD") (pinfunction "LEDVDD_LEDVDD") (pintype "power_in"))
      (node (ref "LED51") (pin "VDD") (pinfunction "VDD_VDD") (pintype "power_in"))
      (node (ref "LED52") (pin "LEDVDD") (pinfunction "LEDVDD_LEDVDD") (pintype "power_in"))
      (node (ref "LED52") (pin "VDD") (pinfunction "VDD_VDD") (pintype "power_in"))
      (node (ref "LED53") (pin "LEDVDD") (pinfunction "LEDVDD_LEDVDD") (pintype "power_in"))
      (node (ref "LED53") (pin "VDD") (pinfunction "VDD_VDD") (pintype "power_in"))
      (node (ref "LED54") (pin "LEDVDD") (pinfunction "LEDVDD_LEDVDD") (pintype "power_in"))
      (node (ref "LED54") (pin "VDD") (pinfunction "VDD_VDD") (pintype "power_in"))
      (node (ref "LED55") (pin "LEDVDD") (pinfunction "LEDVDD_LEDVDD") (pintype "power_in"))
      (node (ref "LED55") (pin "VDD") (pinfunction "VDD_VDD") (pintype "power_in"))
      (node (ref "LED56") (pin "LEDVDD") (pinfunction "LEDVDD_LEDVDD") (pintype "power_in"))
      (node (ref "LED56") (pin "VDD") (pinfunction "VDD_VDD") (pintype "power_in"))
      (node (ref "LED57") (pin "LEDVDD") (pinfunction "LEDVDD_LEDVDD") (pintype "power_in"))
      (node (ref "LED57") (pin "VDD") (pinfunction "VDD_VDD") (pintype "power_in"))
      (node (ref "LED58") (pin "LEDVDD") (pinfunction "LEDVDD_LEDVDD") (pintype "power_in"))
      (node (ref "LED58") (pin "VDD") (pinfunction "VDD_VDD") (pintype "power_in"))
      (node (ref "LED59") (pin "LEDVDD") (pinfunction "LEDVDD_LEDVDD") (pintype "power_in"))
      (node (ref "LED59") (pin "VDD") (pinfunction "VDD_VDD") (pintype "power_in"))
      (node (ref "LED6") (pin "LEDVDD") (pinfunction "LEDVDD_LEDVDD") (pintype "power_in"))
      (node (ref "LED6") (pin "VDD") (pinfunction "VDD_VDD") (pintype "power_in"))
      (node (ref "LED60") (pin "LEDVDD") (pinfunction "LEDVDD_LEDVDD") (pintype "power_in"))
      (node (ref "LED60") (pin "VDD") (pinfunction "VDD_VDD") (pintype "power_in"))
      (node (ref "LED61") (pin "LEDVDD") (pinfunction "LEDVDD_LEDVDD") (pintype "power_in"))
      (node (ref "LED61") (pin "VDD") (pinfunction "VDD_VDD") (pintype "power_in"))
      (node (ref "LED62") (pin "LEDVDD") (pinfunction "LEDVDD_LEDVDD") (pintype "power_in"))
      (node (ref "LED62") (pin "VDD") (pinfunction "VDD_VDD") (pintype "power_in"))
      (node (ref "LED63") (pin "LEDVDD") (pinfunction "LEDVDD_LEDVDD") (pintype "power_in"))
      (node (ref "LED63") (pin "VDD") (pinfunction "VDD_VDD") (pintype "power_in"))
      (node (ref "LED64") (pin "LEDVDD") (pinfunction "LEDVDD_LEDVDD") (pintype "power_in"))
      (node (ref "LED64") (pin "VDD") (pinfunction "VDD_VDD") (pintype "power_in"))
      (node (ref "LED7") (pin "LEDVDD") (pinfunction "LEDVDD_LEDVDD") (pintype "power_in"))
      (node (ref "LED7") (pin "VDD") (pinfunction "VDD_VDD") (pintype "power_in"))
      (node (ref "LED8") (pin "LEDVDD") (pinfunction "LEDVDD_LEDVDD") (pintype "power_in"))
      (node (ref "LED8") (pin "VDD") (pinfunction "VDD_VDD") (pintype "power_in"))
      (node (ref "LED9") (pin "LEDVDD") (pinfunction "LEDVDD_LEDVDD") (pintype "power_in"))
      (node (ref "LED9") (pin "VDD") (pinfunction "VDD_VDD") (pintype "power_in"))
    )
    (net (code "3") (name "Net-(JP1-Pad1)") (class "Default")
      (node (ref "JP1") (pin "1") (pinfunction "1_1") (pintype "passive"))
      (node (ref "LED1") (pin "DI") (pinfunction "DI_DI") (pintype "input"))
    )
    (net (code "4") (name "Net-(LED1-PadDO)") (class "Default")
      (node (ref "LED1") (pin "DO") (pinfunction "DO_DO") (pintype "output"))
      (node (ref "LED2") (pin "DI") (pinfunction "DI_DI") (pintype "input"))
    )
    (net (code "5") (name "Net-(LED2-PadDO)") (class "Default")
      (node (ref "LED2") (pin "DO") (pinfunction "DO_DO") (pintype "output"))
      (node (ref "LED3") (pin "DI") (pinfunction "DI_DI") (pintype "input"))
    )
    (net (code "6") (name "Net-(LED3-PadDO)") (class "Default")
      (node (ref "LED3") (pin "DO") (pinfunction "DO_DO") (pintype "output"))
      (node (ref "LED4") (pin "DI") (pinfunction "DI_DI") (pintype "input"))
    )
    (net (code "7") (name "Net-(LED4-PadDO)") (class "Default")
      (node (ref "LED4") (pin "DO") (pinfunction "DO_DO") (pintype "output"))
      (node (ref "LED5") (pin "DI") (pinfunction "DI_DI") (pintype "input"))
    )
    (net (code "8") (name "Net-(LED5-PadDO)") (class "Default")
      (node (ref "LED5") (pin "DO") (pinfunction "DO_DO") (pintype "output"))
      (node (ref "LED6") (pin "DI") (pinfunction "DI_DI") (pintype "input"))
    )
    (net (code "9") (name "Net-(LED6-PadDO)") (class "Default")
      (node (ref "LED6") (pin "DO") (pinfunction "DO_DO") (pintype "output"))
      (node (ref "LED7") (pin "DI") (pinfunction "DI_DI") (pintype "input"))
    )
    (net (code "10") (name "Net-(LED7-PadDO)") (class "Default")
      (node (ref "LED7") (pin "DO") (pinfunction "DO_DO") (pintype "output"))
      (node (ref "LED8") (pin "DI") (pinfunction "DI_DI") (pintype "input"))
    )
    (net (code "11") (name "Net-(LED8-PadDO)") (class "Default")
      (node (ref "LED8") (pin "DO") (pinfunction "DO_DO") (pintype "output"))
      (node (ref "LED9") (pin "DI") (pinfunction "DI_DI") (pintype "input"))
    )
    (net (code "12") (name "Net-(LED10-PadDI)") (class "Default")
      (node (ref "LED10") (pin "DI") (pinfunction "DI_DI") (pintype "input"))
      (node (ref "LED9") (pin "DO") (pinfunction "DO_DO") (pintype "output"))
    )
    (net (code "13") (name "Net-(LED10-PadDO)") (class "Default")
      (node (ref "LED10") (pin "DO") (pinfunction "DO_DO") (pintype "output"))
      (node (ref "LED11") (pin "DI") (pinfunction "DI_DI") (pintype "input"))
    )
    (net (code "14") (name "Net-(LED11-PadDO)") (class "Default")
      (node (ref "LED11") (pin "DO") (pinfunction "DO_DO") (pintype "output"))
      (node (ref "LED12") (pin "DI") (pinfunction "DI_DI") (pintype "input"))
    )
    (net (code "15") (name "Net-(LED12-PadDO)") (class "Default")
      (node (ref "LED12") (pin "DO") (pinfunction "DO_DO") (pintype "output"))
      (node (ref "LED13") (pin "DI") (pinfunction "DI_DI") (pintype "input"))
    )
    (net (code "16") (name "Net-(LED13-PadDO)") (class "Default")
      (node (ref "LED13") (pin "DO") (pinfunction "DO_DO") (pintype "output"))
      (node (ref "LED14") (pin "DI") (pinfunction "DI_DI") (pintype "input"))
    )
    (net (code "17") (name "Net-(LED14-PadDO)") (class "Default")
      (node (ref "LED14") (pin "DO") (pinfunction "DO_DO") (pintype "output"))
      (node (ref "LED15") (pin "DI") (pinfunction "DI_DI") (pintype "input"))
    )
    (net (code "18") (name "Net-(LED15-PadDO)") (class "Default")
      (node (ref "LED15") (pin "DO") (pinfunction "DO_DO") (pintype "output"))
      (node (ref "LED16") (pin "DI") (pinfunction "DI_DI") (pintype "input"))
    )
    (net (code "19") (name "Net-(LED16-PadDO)") (class "Default")
      (node (ref "LED16") (pin "DO") (pinfunction "DO_DO") (pintype "output"))
      (node (ref "LED17") (pin "DI") (pinfunction "DI_DI") (pintype "input"))
    )
    (net (code "20") (name "Net-(LED17-PadDO)") (class "Default")
      (node (ref "LED17") (pin "DO") (pinfunction "DO_DO") (pintype "output"))
      (node (ref "LED18") (pin "DI") (pinfunction "DI_DI") (pintype "input"))
    )
    (net (code "21") (name "Net-(LED18-PadDO)") (class "Default")
      (node (ref "LED18") (pin "DO") (pinfunction "DO_DO") (pintype "output"))
      (node (ref "LED19") (pin "DI") (pinfunction "DI_DI") (pintype "input"))
    )
    (net (code "22") (name "Net-(LED19-PadDO)") (class "Default")
      (node (ref "LED19") (pin "DO") (pinfunction "DO_DO") (pintype "output"))
      (node (ref "LED20") (pin "DI") (pinfunction "DI_DI") (pintype "input"))
    )
    (net (code "23") (name "Net-(LED20-PadDO)") (class "Default")
      (node (ref "LED20") (pin "DO") (pinfunction "DO_DO") (pintype "output"))
      (node (ref "LED21") (pin "DI") (pinfunction "DI_DI") (pintype "input"))
    )
    (net (code "24") (name "Net-(LED21-PadDO)") (class "Default")
      (node (ref "LED21") (pin "DO") (pinfunction "DO_DO") (pintype "output"))
      (node (ref "LED22") (pin "DI") (pinfunction "DI_DI") (pintype "input"))
    )
    (net (code "25") (name "Net-(LED22-PadDO)") (class "Default")
      (node (ref "LED22") (pin "DO") (pinfunction "DO_DO") (pintype "output"))
      (node (ref "LED23") (pin "DI") (pinfunction "DI_DI") (pintype "input"))
    )
    (net (code "26") (name "Net-(LED23-PadDO)") (class "Default")
      (node (ref "LED23") (pin "DO") (pinfunction "DO_DO") (pintype "output"))
      (node (ref "LED24") (pin "DI") (pinfunction "DI_DI") (pintype "input"))
    )
    (net (code "27") (name "Net-(LED24-PadDO)") (class "Default")
      (node (ref "LED24") (pin "DO") (pinfunction "DO_DO") (pintype "output"))
      (node (ref "LED25") (pin "DI") (pinfunction "DI_DI") (pintype "input"))
    )
    (net (code "28") (name "Net-(LED25-PadDO)") (class "Default")
      (node (ref "LED25") (pin "DO") (pinfunction "DO_DO") (pintype "output"))
      (node (ref "LED26") (pin "DI") (pinfunction "DI_DI") (pintype "input"))
    )
    (net (code "29") (name "Net-(LED26-PadDO)") (class "Default")
      (node (ref "LED26") (pin "DO") (pinfunction "DO_DO") (pintype "output"))
      (node (ref "LED27") (pin "DI") (pinfunction "DI_DI") (pintype "input"))
    )
    (net (code "30") (name "Net-(LED27-PadDO)") (class "Default")
      (node (ref "LED27") (pin "DO") (pinfunction "DO_DO") (pintype "output"))
      (node (ref "LED28") (pin "DI") (pinfunction "DI_DI") (pintype "input"))
    )
    (net (code "31") (name "Net-(LED28-PadDO)") (class "Default")
      (node (ref "LED28") (pin "DO") (pinfunction "DO_DO") (pintype "output"))
      (node (ref "LED29") (pin "DI") (pinfunction "DI_DI") (pintype "input"))
    )
    (net (code "32") (name "Net-(LED29-PadDO)") (class "Default")
      (node (ref "LED29") (pin "DO") (pinfunction "DO_DO") (pintype "output"))
      (node (ref "LED30") (pin "DI") (pinfunction "DI_DI") (pintype "input"))
    )
    (net (code "33") (name "Net-(LED30-PadDO)") (class "Default")
      (node (ref "LED30") (pin "DO") (pinfunction "DO_DO") (pintype "output"))
      (node (ref "LED31") (pin "DI") (pinfunction "DI_DI") (pintype "input"))
    )
    (net (code "34") (name "Net-(LED31-PadDO)") (class "Default")
      (node (ref "LED31") (pin "DO") (pinfunction "DO_DO") (pintype "output"))
      (node (ref "LED32") (pin "DI") (pinfunction "DI_DI") (pintype "input"))
    )
    (net (code "35") (name "Net-(LED32-PadDO)") (class "Default")
      (node (ref "LED32") (pin "DO") (pinfunction "DO_DO") (pintype "output"))
      (node (ref "LED33") (pin "DI") (pinfunction "DI_DI") (pintype "input"))
    )
    (net (code "36") (name "Net-(LED33-PadDO)") (class "Default")
      (node (ref "LED33") (pin "DO") (pinfunction "DO_DO") (pintype "output"))
      (node (ref "LED34") (pin "DI") (pinfunction "DI_DI") (pintype "input"))
    )
    (net (code "37") (name "Net-(LED34-PadDO)") (class "Default")
      (node (ref "LED34") (pin "DO") (pinfunction "DO_DO") (pintype "output"))
      (node (ref "LED35") (pin "DI") (pinfunction "DI_DI") (pintype "input"))
    )
    (net (code "38") (name "Net-(LED35-PadDO)") (class "Default")
      (node (ref "LED35") (pin "DO") (pinfunction "DO_DO") (pintype "output"))
      (node (ref "LED36") (pin "DI") (pinfunction "DI_DI") (pintype "input"))
    )
    (net (code "39") (name "Net-(LED36-PadDO)") (class "Default")
      (node (ref "LED36") (pin "DO") (pinfunction "DO_DO") (pintype "output"))
      (node (ref "LED37") (pin "DI") (pinfunction "DI_DI") (pintype "input"))
    )
    (net (code "40") (name "Net-(LED37-PadDO)") (class "Default")
      (node (ref "LED37") (pin "DO") (pinfunction "DO_DO") (pintype "output"))
      (node (ref "LED38") (pin "DI") (pinfunction "DI_DI") (pintype "input"))
    )
    (net (code "41") (name "Net-(LED38-PadDO)") (class "Default")
      (node (ref "LED38") (pin "DO") (pinfunction "DO_DO") (pintype "output"))
      (node (ref "LED39") (pin "DI") (pinfunction "DI_DI") (pintype "input"))
    )
    (net (code "42") (name "Net-(LED39-PadDO)") (class "Default")
      (node (ref "LED39") (pin "DO") (pinfunction "DO_DO") (pintype "output"))
      (node (ref "LED40") (pin "DI") (pinfunction "DI_DI") (pintype "input"))
    )
    (net (code "43") (name "Net-(LED40-PadDO)") (class "Default")
      (node (ref "LED40") (pin "DO") (pinfunction "DO_DO") (pintype "output"))
      (node (ref "LED41") (pin "DI") (pinfunction "DI_DI") (pintype "input"))
    )
    (net (code "44") (name "Net-(LED41-PadDO)") (class "Default")
      (node (ref "LED41") (pin "DO") (pinfunction "DO_DO") (pintype "output"))
      (node (ref "LED42") (pin "DI") (pinfunction "DI_DI") (pintype "input"))
    )
    (net (code "45") (name "Net-(LED42-PadDO)") (class "Default")
      (node (ref "LED42") (pin "DO") (pinfunction "DO_DO") (pintype "output"))
      (node (ref "LED43") (pin "DI") (pinfunction "DI_DI") (pintype "input"))
    )
    (net (code "46") (name "Net-(LED43-PadDO)") (class "Default")
      (node (ref "LED43") (pin "DO") (pinfunction "DO_DO") (pintype "output"))
      (node (ref "LED44") (pin "DI") (pinfunction "DI_DI") (pintype "input"))
    )
    (net (code "47") (name "Net-(LED44-PadDO)") (class "Default")
      (node (ref "LED44") (pin "DO") (pinfunction "DO_DO") (pintype "output"))
      (node (ref "LED45") (pin "DI") (pinfunction "DI_DI") (pintype "input"))
    )
    (net (code "48") (name "Net-(LED45-PadDO)") (class "Default")
      (node (ref "LED45") (pin "DO") (pinfunction "DO_DO") (pintype "output"))
      (node (ref "LED46") (pin "DI") (pinfunction "DI_DI") (pintype "input"))
    )
    (net (code "49") (name "Net-(LED46-PadDO)") (class "Default")
      (node (ref "LED46") (pin "DO") (pinfunction "DO_DO") (pintype "output"))
      (node (ref "LED47") (pin "DI") (pinfunction "DI_DI") (pintype "input"))
    )
    (net (code "50") (name "Net-(LED47-PadDO)") (class "Default")
      (node (ref "LED47") (pin "DO") (pinfunction "DO_DO") (pintype "output"))
      (node (ref "LED48") (pin "DI") (pinfunction "DI_DI") (pintype "input"))
    )
    (net (code "51") (name "Net-(LED48-PadDO)") (class "Default")
      (node (ref "LED48") (pin "DO") (pinfunction "DO_DO") (pintype "output"))
      (node (ref "LED49") (pin "DI") (pinfunction "DI_DI") (pintype "input"))
    )
    (net (code "52") (name "Net-(LED49-PadDO)") (class "Default")
      (node (ref "LED49") (pin "DO") (pinfunction "DO_DO") (pintype "output"))
      (node (ref "LED50") (pin "DI") (pinfunction "DI_DI") (pintype "input"))
    )
    (net (code "53") (name "Net-(LED50-PadDO)") (class "Default")
      (node (ref "LED50") (pin "DO") (pinfunction "DO_DO") (pintype "output"))
      (node (ref "LED51") (pin "DI") (pinfunction "DI_DI") (pintype "input"))
    )
    (net (code "54") (name "Net-(LED51-PadDO)") (class "Default")
      (node (ref "LED51") (pin "DO") (pinfunction "DO_DO") (pintype "output"))
      (node (ref "LED52") (pin "DI") (pinfunction "DI_DI") (pintype "input"))
    )
    (net (code "55") (name "Net-(LED52-PadDO)") (class "Default")
      (node (ref "LED52") (pin "DO") (pinfunction "DO_DO") (pintype "output"))
      (node (ref "LED53") (pin "DI") (pinfunction "DI_DI") (pintype "input"))
    )
    (net (code "56") (name "Net-(LED53-PadDO)") (class "Default")
      (node (ref "LED53") (pin "DO") (pinfunction "DO_DO") (pintype "output"))
      (node (ref "LED54") (pin "DI") (pinfunction "DI_DI") (pintype "input"))
    )
    (net (code "57") (name "Net-(LED54-PadDO)") (class "Default")
      (node (ref "LED54") (pin "DO") (pinfunction "DO_DO") (pintype "output"))
      (node (ref "LED55") (pin "DI") (pinfunction "DI_DI") (pintype "input"))
    )
    (net (code "58") (name "Net-(LED55-PadDO)") (class "Default")
      (node (ref "LED55") (pin "DO") (pinfunction "DO_DO") (pintype "output"))
      (node (ref "LED56") (pin "DI") (pinfunction "DI_DI") (pintype "input"))
    )
    (net (code "59") (name "Net-(LED56-PadDO)") (class "Default")
      (node (ref "LED56") (pin "DO") (pinfunction "DO_DO") (pintype "output"))
      (node (ref "LED57") (pin "DI") (pinfunction "DI_DI") (pintype "input"))
    )
    (net (code "60") (name "Net-(LED57-PadDO)") (class "Default")
      (node (ref "LED57") (pin "DO") (pinfunction "DO_DO") (pintype "output"))
      (node (ref "LED58") (pin "DI") (pinfunction "DI_DI") (pintype "input"))
    )
    (net (code "61") (name "Net-(LED58-PadDO)") (class "Default")
      (node (ref "LED58") (pin "DO") (pinfunction "DO_DO") (pintype "output"))
      (node (ref "LED59") (pin "DI") (pinfunction "DI_DI") (pintype "input"))
    )
    (net (code "62") (name "Net-(LED59-PadDO)") (class "Default")
      (node (ref "LED59") (pin "DO") (pinfunction "DO_DO") (pintype "output"))
      (node (ref "LED60") (pin "DI") (pinfunction "DI_DI") (pintype "input"))
    )
    (net (code "63") (name "Net-(LED60-PadDO)") (class "Default")
      (node (ref "LED60") (pin "DO") (pinfunction "DO_DO") (pintype "output"))
      (node (ref "LED61") (pin "DI") (pinfunction "DI_DI") (pintype "input"))
    )
    (net (code "64") (name "Net-(LED61-PadDO)") (class "Default")
      (node (ref "LED61") (pin "DO") (pinfunction "DO_DO") (pintype "output"))
      (node (ref "LED62") (pin "DI") (pinfunction "DI_DI") (pintype "input"))
    )
    (net (code "65") (name "Net-(LED62-PadDO)") (class "Default")
      (node (ref "LED62") (pin "DO") (pinfunction "DO_DO") (pintype "output"))
      (node (ref "LED63") (pin "DI") (pinfunction "DI_DI") (pintype "input"))
    )
    (net (code "66") (name "Net-(LED63-PadDO)") (class "Default")
      (node (ref "LED63") (pin "DO") (pinfunction "DO_DO") (pintype "output"))
      (node (ref "LED64") (pin "DI") (pinfunction "DI_DI") (pintype "input"))
    )
    (net (code "67") (name "unconnected-(JP2-Pad1)") (class "Default")
      (node (ref "JP2") (pin "1") (pinfunction "1_1") (pintype "passive"))
    )
    (net (code "68") (name "unconnected-(JP3-Pad1)") (class "Default")
      (node (ref "JP3") (pin "1") (pinfunction "1_1") (pintype "passive"))
    )
    (net (code "69") (name "unconnected-(LED64-PadDO)") (class "Default")
      (node (ref "LED64") (pin "DO") (pinfunction "DO_DO") (pintype "output"))
    )
  )
)
